# LED_schematic.net
KiCad netlist of a schematic drawn in Altium Designer
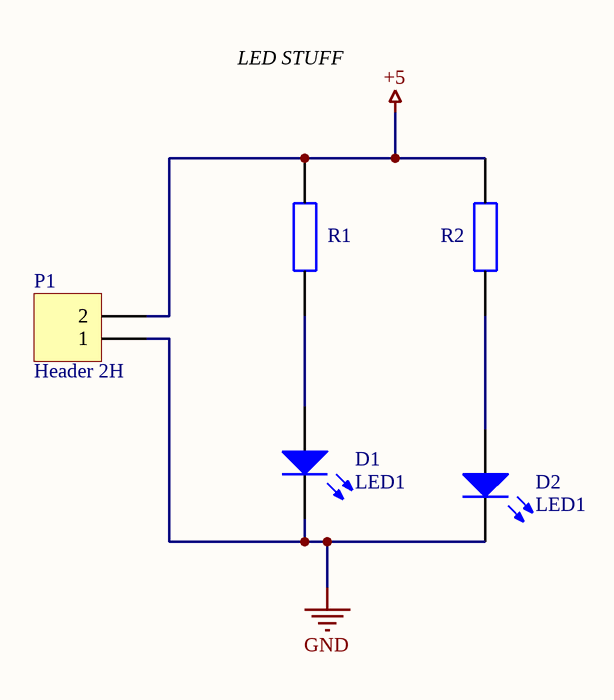
[diagram p0: LED_schematic.SchDoc]

(export (version "E")
  (design (tool "Eeschema 10.0.6"))
  (components
    (comp (ref "D1")
      (value "LED1")
      (footprint "LED-1")
      (description "Typical RED GaAs LED")
      (fields (field (name "PUBLISHER") "Altium Limited"))
      (libsource (lib "Miscellaneous Devices") (part "LED1"))
    )
    (comp (ref "D2")
      (value "LED1")
      (footprint "LED-1")
      (description "Typical RED GaAs LED")
      (fields (field (name "PUBLISHER") "Altium Limited"))
      (libsource (lib "Miscellaneous Devices") (part "LED1"))
    )
    (comp (ref "P1")
      (value "Header 2H")
      (footprint "HDR1X2H")
      (description "Header, 2-Pin, Right Angle")
      (fields (field (name "PUBLISHER") "Altium Limited"))
      (libsource (lib "Miscellaneous Connectors") (part "Header 2H"))
    )
    (comp (ref "R1")
      (value "KTR10EZPF5103")
      (footprint "RESC2012X65N")
      (description "Thick Film Resistors - SMD 0805 510Kohm 1% High VoltageAEC-Q200")
      (libsource (lib "KTR10EZPF5103") (part "KTR10EZPF5103"))
    )
    (comp (ref "R2")
      (value "KTR10EZPF5103")
      (footprint "RESC2012X65N")
      (description "Thick Film Resistors - SMD 0805 510Kohm 1% High VoltageAEC-Q200")
      (libsource (lib "KTR10EZPF5103") (part "KTR10EZPF5103"))
    )
  )
  (nets
    (net (code "1") (name "+5") (class "Default")
      (node (ref "P1") (pin "2") (pinfunction "2_2") (pintype "passive"))
      (node (ref "R1") (pin "2") (pinfunction "2_2") (pintype "passive"))
      (node (ref "R2") (pin "2") (pinfunction "2_2") (pintype "passive"))
    )
    (net (code "2") (name "GND") (class "Default")
      (node (ref "D1") (pin "2") (pinfunction "K_2") (pintype "passive"))
      (node (ref "D2") (pin "2") (pinfunction "K_2") (pintype "passive"))
      (node (ref "P1") (pin "1") (pinfunction "1_1") (pintype "passive"))
    )
    (net (code "3") (name "Net-(D1-A)") (class "Default")
      (node (ref "D1") (pin "1") (pinfunction "A_1") (pintype "passive"))
      (node (ref "R1") (pin "1") (pinfunction "1_1") (pintype "passive"))
    )
    (net (code "4") (name "Net-(D2-A)") (class "Default")
      (node (ref "D2") (pin "1") (pinfunction "A_1") (pintype "passive"))
      (node (ref "R2") (pin "1") (pinfunction "1_1") (pintype "passive"))
    )
  )
)
